# mutex.net
KiCad netlist of a schematic drawn in EAGLE
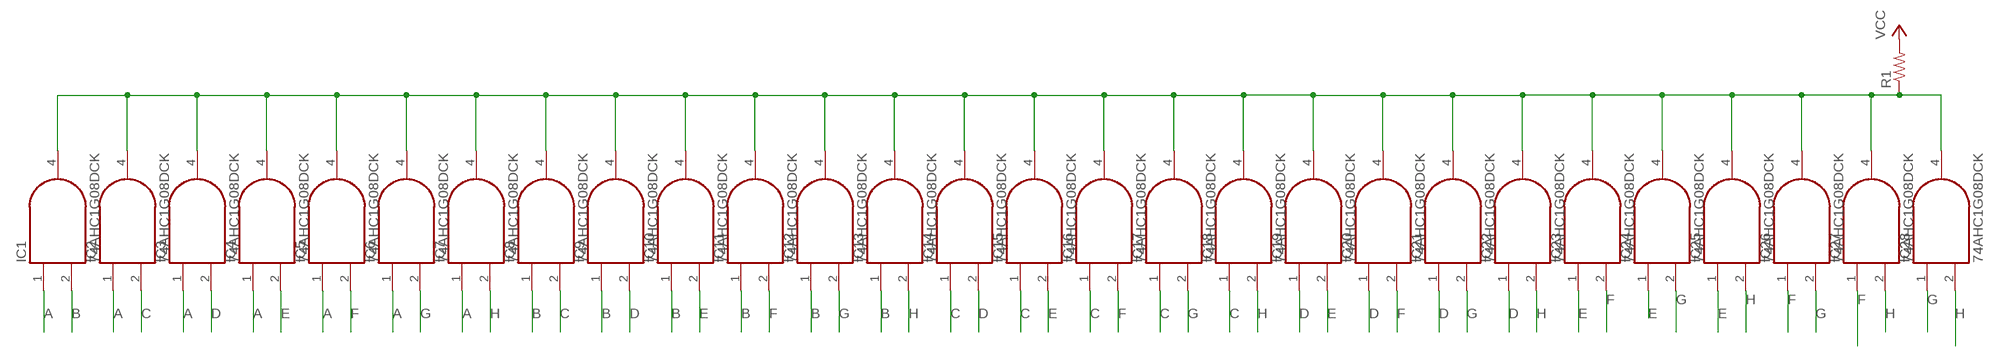
[diagram p0: schematic, sheet 1]

(export (version "E")
  (design (tool "Eeschema 10.0.6"))
  (components
    (comp (ref "IC1")
      (value "74AHC1G08DCK")
      (footprint "eagle-import:SC70-5")
      (libsource (lib "eagle-import") (part "741G08DCKAHC"))
    )
    (comp (ref "IC2")
      (value "74AHC1G08DCK")
      (footprint "eagle-import:SC70-5")
      (libsource (lib "eagle-import") (part "741G08DCKAHC"))
    )
    (comp (ref "IC3")
      (value "74AHC1G08DCK")
      (footprint "eagle-import:SC70-5")
      (libsource (lib "eagle-import") (part "741G08DCKAHC"))
    )
    (comp (ref "IC4")
      (value "74AHC1G08DCK")
      (footprint "eagle-import:SC70-5")
      (libsource (lib "eagle-import") (part "741G08DCKAHC"))
    )
    (comp (ref "IC5")
      (value "74AHC1G08DCK")
      (footprint "eagle-import:SC70-5")
      (libsource (lib "eagle-import") (part "741G08DCKAHC"))
    )
    (comp (ref "IC6")
      (value "74AHC1G08DCK")
      (footprint "eagle-import:SC70-5")
      (libsource (lib "eagle-import") (part "741G08DCKAHC"))
    )
    (comp (ref "IC7")
      (value "74AHC1G08DCK")
      (footprint "eagle-import:SC70-5")
      (libsource (lib "eagle-import") (part "741G08DCKAHC"))
    )
    (comp (ref "IC8")
      (value "74AHC1G08DCK")
      (footprint "eagle-import:SC70-5")
      (libsource (lib "eagle-import") (part "741G08DCKAHC"))
    )
    (comp (ref "IC9")
      (value "74AHC1G08DCK")
      (footprint "eagle-import:SC70-5")
      (libsource (lib "eagle-import") (part "741G08DCKAHC"))
    )
    (comp (ref "IC10")
      (value "74AHC1G08DCK")
      (footprint "eagle-import:SC70-5")
      (libsource (lib "eagle-import") (part "741G08DCKAHC"))
    )
    (comp (ref "IC11")
      (value "74AHC1G08DCK")
      (footprint "eagle-import:SC70-5")
      (libsource (lib "eagle-import") (part "741G08DCKAHC"))
    )
    (comp (ref "IC12")
      (value "74AHC1G08DCK")
      (footprint "eagle-import:SC70-5")
      (libsource (lib "eagle-import") (part "741G08DCKAHC"))
    )
    (comp (ref "IC13")
      (value "74AHC1G08DCK")
      (footprint "eagle-import:SC70-5")
      (libsource (lib "eagle-import") (part "741G08DCKAHC"))
    )
    (comp (ref "IC14")
      (value "74AHC1G08DCK")
      (footprint "eagle-import:SC70-5")
      (libsource (lib "eagle-import") (part "741G08DCKAHC"))
    )
    (comp (ref "IC15")
      (value "74AHC1G08DCK")
      (footprint "eagle-import:SC70-5")
      (libsource (lib "eagle-import") (part "741G08DCKAHC"))
    )
    (comp (ref "IC16")
      (value "74AHC1G08DCK")
      (footprint "eagle-import:SC70-5")
      (libsource (lib "eagle-import") (part "741G08DCKAHC"))
    )
    (comp (ref "IC17")
      (value "74AHC1G08DCK")
      (footprint "eagle-import:SC70-5")
      (libsource (lib "eagle-import") (part "741G08DCKAHC"))
    )
    (comp (ref "IC18")
      (value "74AHC1G08DCK")
      (footprint "eagle-import:SC70-5")
      (libsource (lib "eagle-import") (part "741G08DCKAHC"))
    )
    (comp (ref "IC19")
      (value "74AHC1G08DCK")
      (footprint "eagle-import:SC70-5")
      (libsource (lib "eagle-import") (part "741G08DCKAHC"))
    )
    (comp (ref "IC20")
      (value "74AHC1G08DCK")
      (footprint "eagle-import:SC70-5")
      (libsource (lib "eagle-import") (part "741G08DCKAHC"))
    )
    (comp (ref "IC21")
      (value "74AHC1G08DCK")
      (footprint "eagle-import:SC70-5")
      (libsource (lib "eagle-import") (part "741G08DCKAHC"))
    )
    (comp (ref "IC22")
      (value "74AHC1G08DCK")
      (footprint "eagle-import:SC70-5")
      (libsource (lib "eagle-import") (part "741G08DCKAHC"))
    )
    (comp (ref "IC23")
      (value "74AHC1G08DCK")
      (footprint "eagle-import:SC70-5")
      (libsource (lib "eagle-import") (part "741G08DCKAHC"))
    )
    (comp (ref "IC24")
      (value "74AHC1G08DCK")
      (footprint "eagle-import:SC70-5")
      (libsource (lib "eagle-import") (part "741G08DCKAHC"))
    )
    (comp (ref "IC25")
      (value "74AHC1G08DCK")
      (footprint "eagle-import:SC70-5")
      (libsource (lib "eagle-import") (part "741G08DCKAHC"))
    )
    (comp (ref "IC26")
      (value "74AHC1G08DCK")
      (footprint "eagle-import:SC70-5")
      (libsource (lib "eagle-import") (part "741G08DCKAHC"))
    )
    (comp (ref "IC27")
      (value "74AHC1G08DCK")
      (footprint "eagle-import:SC70-5")
      (libsource (lib "eagle-import") (part "741G08DCKAHC"))
    )
    (comp (ref "IC28")
      (value "74AHC1G08DCK")
      (footprint "eagle-import:SC70-5")
      (libsource (lib "eagle-import") (part "741G08DCKAHC"))
    )
    (comp (ref "R1")
      (value "R-US_0207/7")
      (footprint "eagle-import:0207_7")
      (libsource (lib "eagle-import") (part "R-US_0207/7"))
    )
  )
  (nets
    (net (code "1") (name "/A") (class "Default")
      (node (ref "IC1") (pin "1") (pinfunction "I0_1") (pintype "input"))
      (node (ref "IC2") (pin "1") (pinfunction "I0_1") (pintype "input"))
      (node (ref "IC3") (pin "1") (pinfunction "I0_1") (pintype "input"))
      (node (ref "IC4") (pin "1") (pinfunction "I0_1") (pintype "input"))
      (node (ref "IC5") (pin "1") (pinfunction "I0_1") (pintype "input"))
      (node (ref "IC6") (pin "1") (pinfunction "I0_1") (pintype "input"))
      (node (ref "IC7") (pin "1") (pinfunction "I0_1") (pintype "input"))
    )
    (net (code "2") (name "/B") (class "Default")
      (node (ref "IC1") (pin "2") (pinfunction "I1_2") (pintype "input"))
      (node (ref "IC10") (pin "1") (pinfunction "I0_1") (pintype "input"))
      (node (ref "IC11") (pin "1") (pinfunction "I0_1") (pintype "input"))
      (node (ref "IC12") (pin "1") (pinfunction "I0_1") (pintype "input"))
      (node (ref "IC13") (pin "1") (pinfunction "I0_1") (pintype "input"))
      (node (ref "IC8") (pin "1") (pinfunction "I0_1") (pintype "input"))
      (node (ref "IC9") (pin "1") (pinfunction "I0_1") (pintype "input"))
    )
    (net (code "3") (name "/C") (class "Default")
      (node (ref "IC14") (pin "1") (pinfunction "I0_1") (pintype "input"))
      (node (ref "IC15") (pin "1") (pinfunction "I0_1") (pintype "input"))
      (node (ref "IC16") (pin "1") (pinfunction "I0_1") (pintype "input"))
      (node (ref "IC17") (pin "1") (pinfunction "I0_1") (pintype "input"))
      (node (ref "IC18") (pin "1") (pinfunction "I0_1") (pintype "input"))
      (node (ref "IC2") (pin "2") (pinfunction "I1_2") (pintype "input"))
      (node (ref "IC8") (pin "2") (pinfunction "I1_2") (pintype "input"))
    )
    (net (code "4") (name "/D") (class "Default")
      (node (ref "IC14") (pin "2") (pinfunction "I1_2") (pintype "input"))
      (node (ref "IC19") (pin "1") (pinfunction "I0_1") (pintype "input"))
      (node (ref "IC20") (pin "1") (pinfunction "I0_1") (pintype "input"))
      (node (ref "IC21") (pin "1") (pinfunction "I0_1") (pintype "input"))
      (node (ref "IC22") (pin "1") (pinfunction "I0_1") (pintype "input"))
      (node (ref "IC3") (pin "2") (pinfunction "I1_2") (pintype "input"))
      (node (ref "IC9") (pin "2") (pinfunction "I1_2") (pintype "input"))
    )
    (net (code "5") (name "/E") (class "Default")
      (node (ref "IC10") (pin "2") (pinfunction "I1_2") (pintype "input"))
      (node (ref "IC15") (pin "2") (pinfunction "I1_2") (pintype "input"))
      (node (ref "IC19") (pin "2") (pinfunction "I1_2") (pintype "input"))
      (node (ref "IC23") (pin "1") (pinfunction "I0_1") (pintype "input"))
      (node (ref "IC24") (pin "1") (pinfunction "I0_1") (pintype "input"))
      (node (ref "IC25") (pin "1") (pinfunction "I0_1") (pintype "input"))
      (node (ref "IC4") (pin "2") (pinfunction "I1_2") (pintype "input"))
    )
    (net (code "6") (name "/F") (class "Default")
      (node (ref "IC11") (pin "2") (pinfunction "I1_2") (pintype "input"))
      (node (ref "IC16") (pin "2") (pinfunction "I1_2") (pintype "input"))
      (node (ref "IC20") (pin "2") (pinfunction "I1_2") (pintype "input"))
      (node (ref "IC23") (pin "2") (pinfunction "I1_2") (pintype "input"))
      (node (ref "IC26") (pin "1") (pinfunction "I0_1") (pintype "input"))
      (node (ref "IC27") (pin "1") (pinfunction "I0_1") (pintype "input"))
      (node (ref "IC5") (pin "2") (pinfunction "I1_2") (pintype "input"))
    )
    (net (code "7") (name "/G") (class "Default")
      (node (ref "IC12") (pin "2") (pinfunction "I1_2") (pintype "input"))
      (node (ref "IC17") (pin "2") (pinfunction "I1_2") (pintype "input"))
      (node (ref "IC21") (pin "2") (pinfunction "I1_2") (pintype "input"))
      (node (ref "IC24") (pin "2") (pinfunction "I1_2") (pintype "input"))
      (node (ref "IC26") (pin "2") (pinfunction "I1_2") (pintype "input"))
      (node (ref "IC28") (pin "1") (pinfunction "I0_1") (pintype "input"))
      (node (ref "IC6") (pin "2") (pinfunction "I1_2") (pintype "input"))
    )
    (net (code "8") (name "/H") (class "Default")
      (node (ref "IC13") (pin "2") (pinfunction "I1_2") (pintype "input"))
      (node (ref "IC18") (pin "2") (pinfunction "I1_2") (pintype "input"))
      (node (ref "IC22") (pin "2") (pinfunction "I1_2") (pintype "input"))
      (node (ref "IC25") (pin "2") (pinfunction "I1_2") (pintype "input"))
      (node (ref "IC27") (pin "2") (pinfunction "I1_2") (pintype "input"))
      (node (ref "IC28") (pin "2") (pinfunction "I1_2") (pintype "input"))
      (node (ref "IC7") (pin "2") (pinfunction "I1_2") (pintype "input"))
    )
    (net (code "9") (name "Net-(IC10A-O)") (class "Default")
      (node (ref "IC1") (pin "4") (pinfunction "O_4") (pintype "output"))
      (node (ref "IC10") (pin "4") (pinfunction "O_4") (pintype "output"))
      (node (ref "IC11") (pin "4") (pinfunction "O_4") (pintype "output"))
      (node (ref "IC12") (pin "4") (pinfunction "O_4") (pintype "output"))
      (node (ref "IC13") (pin "4") (pinfunction "O_4") (pintype "output"))
      (node (ref "IC14") (pin "4") (pinfunction "O_4") (pintype "output"))
      (node (ref "IC15") (pin "4") (pinfunction "O_4") (pintype "output"))
      (node (ref "IC16") (pin "4") (pinfunction "O_4") (pintype "output"))
      (node (ref "IC17") (pin "4") (pinfunction "O_4") (pintype "output"))
      (node (ref "IC18") (pin "4") (pinfunction "O_4") (pintype "output"))
      (node (ref "IC19") (pin "4") (pinfunction "O_4") (pintype "output"))
      (node (ref "IC2") (pin "4") (pinfunction "O_4") (pintype "output"))
      (node (ref "IC20") (pin "4") (pinfunction "O_4") (pintype "output"))
      (node (ref "IC21") (pin "4") (pinfunction "O_4") (pintype "output"))
      (node (ref "IC22") (pin "4") (pinfunction "O_4") (pintype "output"))
      (node (ref "IC23") (pin "4") (pinfunction "O_4") (pintype "output"))
      (node (ref "IC24") (pin "4") (pinfunction "O_4") (pintype "output"))
      (node (ref "IC25") (pin "4") (pinfunction "O_4") (pintype "output"))
      (node (ref "IC26") (pin "4") (pinfunction "O_4") (pintype "output"))
      (node (ref "IC27") (pin "4") (pinfunction "O_4") (pintype "output"))
      (node (ref "IC28") (pin "4") (pinfunction "O_4") (pintype "output"))
      (node (ref "IC3") (pin "4") (pinfunction "O_4") (pintype "output"))
      (node (ref "IC4") (pin "4") (pinfunction "O_4") (pintype "output"))
      (node (ref "IC5") (pin "4") (pinfunction "O_4") (pintype "output"))
      (node (ref "IC6") (pin "4") (pinfunction "O_4") (pintype "output"))
      (node (ref "IC7") (pin "4") (pinfunction "O_4") (pintype "output"))
      (node (ref "IC8") (pin "4") (pinfunction "O_4") (pintype "output"))
      (node (ref "IC9") (pin "4") (pinfunction "O_4") (pintype "output"))
      (node (ref "R1") (pin "1") (pinfunction "1_1") (pintype "passive"))
    )
    (net (code "10") (name "VCC") (class "Default")
      (node (ref "R1") (pin "2") (pinfunction "2_2") (pintype "passive"))
    )
  )
)
